# main.net
KiCad netlist of a schematic drawn in Altium Designer
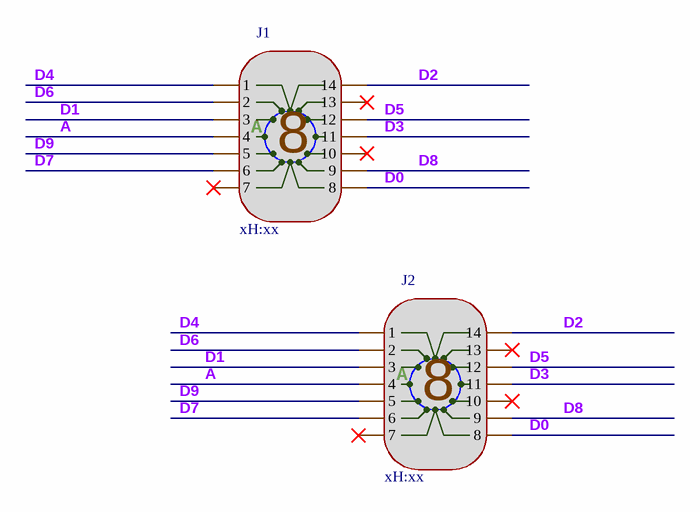
[diagram p0: main.SchDoc]

(export (version "E")
  (design (tool "Eeschema 10.0.6"))
  (components
    (comp (ref "J1")
      (value "xH:xx")
      (footprint "SOCKET_NIXI_TUBE")
      (fields (field (name "PUBLISHER") "Develer srl"))
      (libsource (lib "develer_connectors") (part "NIXIE_TUBE_SOCKET_14PIN_31MM_THD"))
    )
    (comp (ref "J2")
      (value "xH:xx")
      (footprint "SOCKET_NIXI_TUBE_D18")
      (fields (field (name "PUBLISHER") "Develer srl"))
      (libsource (lib "develer_connectors") (part "NIXIE_TUBE_SOCKET_14PIN_31MM_THD"))
    )
  )
  (nets
    (net (code "1") (name "/A") (class "Default")
      (node (ref "J1") (pin "4") (pinfunction "4_4") (pintype "passive"))
      (node (ref "J2") (pin "4") (pinfunction "4_4") (pintype "passive"))
    )
    (net (code "2") (name "/D0") (class "Default")
      (node (ref "J1") (pin "8") (pinfunction "8_8") (pintype "passive"))
      (node (ref "J2") (pin "8") (pinfunction "8_8") (pintype "passive"))
    )
    (net (code "3") (name "/D1") (class "Default")
      (node (ref "J1") (pin "3") (pinfunction "3_3") (pintype "passive"))
      (node (ref "J2") (pin "3") (pinfunction "3_3") (pintype "passive"))
    )
    (net (code "4") (name "/D2") (class "Default")
      (node (ref "J1") (pin "14") (pinfunction "14_14") (pintype "passive"))
      (node (ref "J2") (pin "14") (pinfunction "14_14") (pintype "passive"))
    )
    (net (code "5") (name "/D3") (class "Default")
      (node (ref "J1") (pin "11") (pinfunction "11_11") (pintype "passive"))
      (node (ref "J2") (pin "11") (pinfunction "11_11") (pintype "passive"))
    )
    (net (code "6") (name "/D4") (class "Default")
      (node (ref "J1") (pin "1") (pinfunction "1_1") (pintype "passive"))
      (node (ref "J2") (pin "1") (pinfunction "1_1") (pintype "passive"))
    )
    (net (code "7") (name "/D5") (class "Default")
      (node (ref "J1") (pin "12") (pinfunction "12_12") (pintype "passive"))
      (node (ref "J2") (pin "12") (pinfunction "12_12") (pintype "passive"))
    )
    (net (code "8") (name "/D6") (class "Default")
      (node (ref "J1") (pin "2") (pinfunction "2_2") (pintype "passive"))
      (node (ref "J2") (pin "2") (pinfunction "2_2") (pintype "passive"))
    )
    (net (code "9") (name "/D7") (class "Default")
      (node (ref "J1") (pin "6") (pinfunction "6_6") (pintype "passive"))
      (node (ref "J2") (pin "6") (pinfunction "6_6") (pintype "passive"))
    )
    (net (code "10") (name "/D8") (class "Default")
      (node (ref "J1") (pin "9") (pinfunction "9_9") (pintype "passive"))
      (node (ref "J2") (pin "9") (pinfunction "9_9") (pintype "passive"))
    )
    (net (code "11") (name "/D9") (class "Default")
      (node (ref "J1") (pin "5") (pinfunction "5_5") (pintype "passive"))
      (node (ref "J2") (pin "5") (pinfunction "5_5") (pintype "passive"))
    )
    (net (code "12") (name "unconnected-(J1-Pad7)") (class "Default")
      (node (ref "J1") (pin "7") (pinfunction "7_7") (pintype "passive+no_connect"))
    )
    (net (code "13") (name "unconnected-(J1-Pad10)") (class "Default")
      (node (ref "J1") (pin "10") (pinfunction "10_10") (pintype "passive+no_connect"))
    )
    (net (code "14") (name "unconnected-(J1-Pad13)") (class "Default")
      (node (ref "J1") (pin "13") (pinfunction "13_13") (pintype "passive+no_connect"))
    )
    (net (code "15") (name "unconnected-(J2-Pad7)") (class "Default")
      (node (ref "J2") (pin "7") (pinfunction "7_7") (pintype "passive+no_connect"))
    )
    (net (code "16") (name "unconnected-(J2-Pad10)") (class "Default")
      (node (ref "J2") (pin "10") (pinfunction "10_10") (pintype "passive+no_connect"))
    )
    (net (code "17") (name "unconnected-(J2-Pad13)") (class "Default")
      (node (ref "J2") (pin "13") (pinfunction "13_13") (pintype "passive+no_connect"))
    )
  )
)
